# Pacman2-OSH-panels.net
KiCad netlist of a schematic drawn in EAGLE
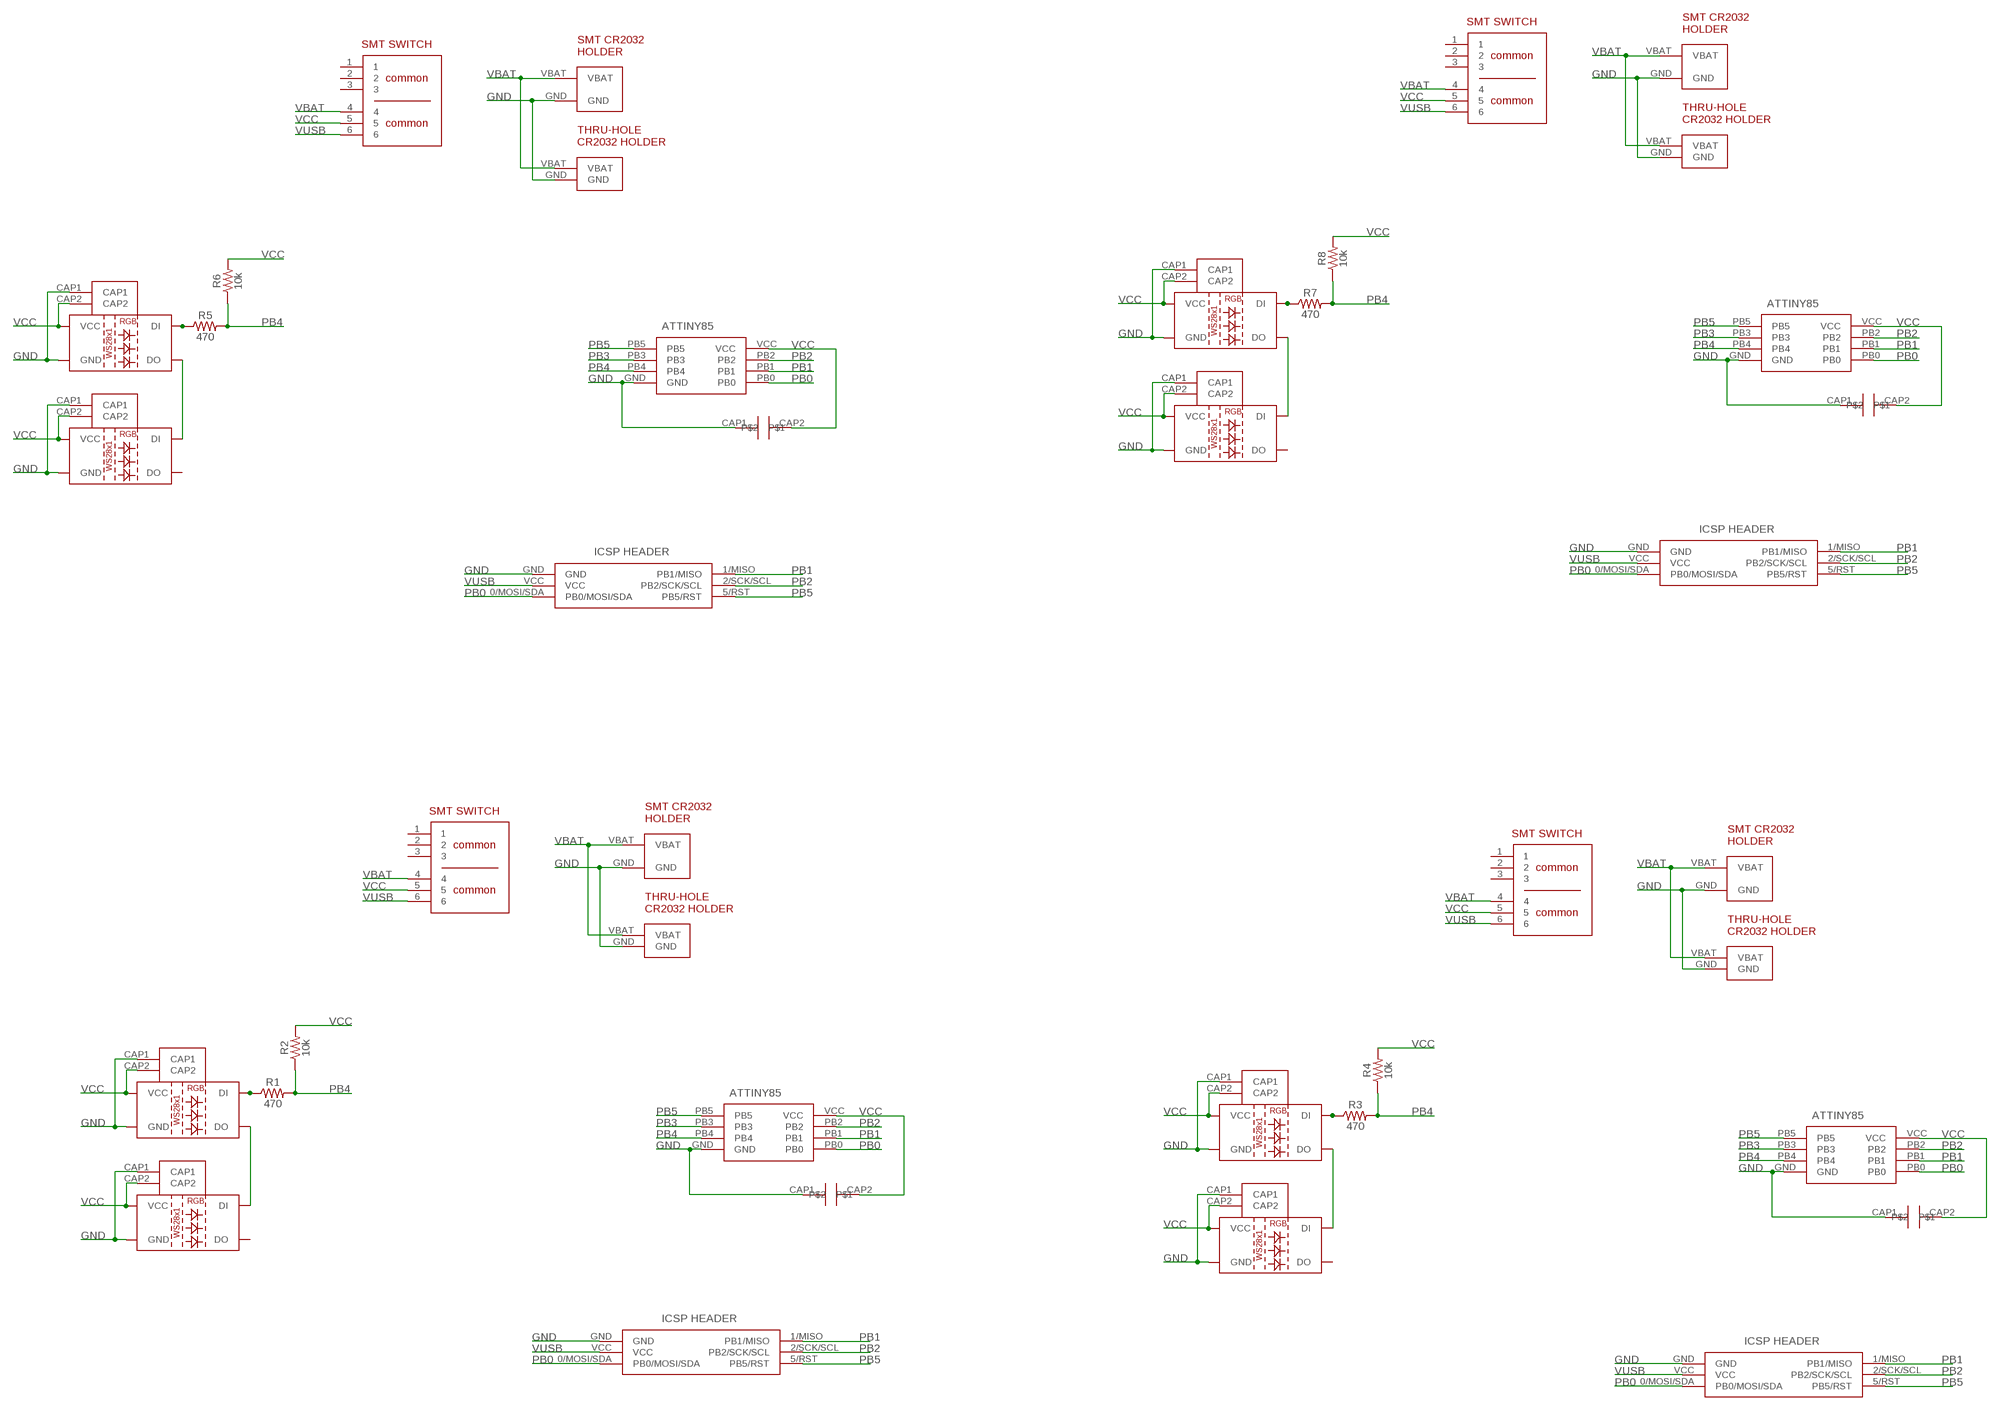
[diagram p0: schematic, sheet 1]

(export (version "E")
  (design (tool "Eeschema 10.0.6"))
  (components
    (comp (ref "D1")
      (value "WS2812B")
      (footprint "eagle-import:WS2812B")
      (libsource (lib "eagle-import") (part "WS2812B"))
    )
    (comp (ref "D2")
      (value "WS2812B")
      (footprint "eagle-import:WS2812B")
      (libsource (lib "eagle-import") (part "WS2812B"))
    )
    (comp (ref "D3")
      (value "WS2812B")
      (footprint "eagle-import:WS2812B")
      (libsource (lib "eagle-import") (part "WS2812B"))
    )
    (comp (ref "D4")
      (value "WS2812B")
      (footprint "eagle-import:WS2812B")
      (libsource (lib "eagle-import") (part "WS2812B"))
    )
    (comp (ref "D5")
      (value "WS2812B")
      (footprint "eagle-import:WS2812B")
      (libsource (lib "eagle-import") (part "WS2812B"))
    )
    (comp (ref "D6")
      (value "WS2812B")
      (footprint "eagle-import:WS2812B")
      (libsource (lib "eagle-import") (part "WS2812B"))
    )
    (comp (ref "D7")
      (value "WS2812B")
      (footprint "eagle-import:WS2812B")
      (libsource (lib "eagle-import") (part "WS2812B"))
    )
    (comp (ref "D8")
      (value "WS2812B")
      (footprint "eagle-import:WS2812B")
      (libsource (lib "eagle-import") (part "WS2812B"))
    )
    (comp (ref "DECOUPLER")
      (value ".1uf")
      (footprint "eagle-import:0603-CAP")
      (libsource (lib "eagle-import") (part "0603-CAP"))
    )
    (comp (ref "DECOUPLER1")
      (value ".1uf")
      (footprint "eagle-import:0603-CAP")
      (libsource (lib "eagle-import") (part "0603-CAP"))
    )
    (comp (ref "DECOUPLER2")
      (value ".1uf")
      (footprint "eagle-import:0603-CAP")
      (libsource (lib "eagle-import") (part "0603-CAP"))
    )
    (comp (ref "DECOUPLER3")
      (value ".1uf")
      (footprint "eagle-import:0603-CAP")
      (libsource (lib "eagle-import") (part "0603-CAP"))
    )
    (comp (ref "IC1")
      (value "ATTINY85-20SU")
      (footprint "eagle-import:SOT127P798X216-8N")
      (fields (field (name "RS_PART_NUMBER") "1331674"))
      (libsource (lib "eagle-import") (part "ATTINY85-20SU"))
    )
    (comp (ref "IC2")
      (value "ATTINY85-20SU")
      (footprint "eagle-import:SOT127P798X216-8N")
      (fields (field (name "RS_PART_NUMBER") "1331674"))
      (libsource (lib "eagle-import") (part "ATTINY85-20SU"))
    )
    (comp (ref "IC3")
      (value "ATTINY85-20SU")
      (footprint "eagle-import:SOT127P798X216-8N")
      (fields (field (name "RS_PART_NUMBER") "1331674"))
      (libsource (lib "eagle-import") (part "ATTINY85-20SU"))
    )
    (comp (ref "IC4")
      (value "ATTINY85-20SU")
      (footprint "eagle-import:SOT127P798X216-8N")
      (fields (field (name "RS_PART_NUMBER") "1331674"))
      (libsource (lib "eagle-import") (part "ATTINY85-20SU"))
    )
    (comp (ref "J1")
      (value "ICSP-LO-SILK")
      (footprint "eagle-import:ICSP-LO-SILK")
      (libsource (lib "eagle-import") (part "ICSP-LO-SILK"))
    )
    (comp (ref "J2")
      (value "ICSP-LO-SILK")
      (footprint "eagle-import:ICSP-LO-SILK")
      (libsource (lib "eagle-import") (part "ICSP-LO-SILK"))
    )
    (comp (ref "J3")
      (value "ICSP-LO-SILK")
      (footprint "eagle-import:ICSP-LO-SILK")
      (libsource (lib "eagle-import") (part "ICSP-LO-SILK"))
    )
    (comp (ref "J4")
      (value "ICSP-LO-SILK")
      (footprint "eagle-import:ICSP-LO-SILK")
      (libsource (lib "eagle-import") (part "ICSP-LO-SILK"))
    )
    (comp (ref "R1")
      (value "470")
      (footprint "eagle-import:0603")
      (libsource (lib "eagle-import") (part "470OHM-0603-1/10W-1%"))
    )
    (comp (ref "R2")
      (value "10k")
      (footprint "eagle-import:0603")
      (libsource (lib "eagle-import") (part "10KOHM-0603-1/10W-1%"))
    )
    (comp (ref "R3")
      (value "470")
      (footprint "eagle-import:0603")
      (libsource (lib "eagle-import") (part "470OHM-0603-1/10W-1%"))
    )
    (comp (ref "R4")
      (value "10k")
      (footprint "eagle-import:0603")
      (libsource (lib "eagle-import") (part "10KOHM-0603-1/10W-1%"))
    )
    (comp (ref "R5")
      (value "470")
      (footprint "eagle-import:0603")
      (libsource (lib "eagle-import") (part "470OHM-0603-1/10W-1%"))
    )
    (comp (ref "R6")
      (value "10k")
      (footprint "eagle-import:0603")
      (libsource (lib "eagle-import") (part "10KOHM-0603-1/10W-1%"))
    )
    (comp (ref "R7")
      (value "470")
      (footprint "eagle-import:0603")
      (libsource (lib "eagle-import") (part "470OHM-0603-1/10W-1%"))
    )
    (comp (ref "R8")
      (value "10k")
      (footprint "eagle-import:0603")
      (libsource (lib "eagle-import") (part "10KOHM-0603-1/10W-1%"))
    )
    (comp (ref "U$1")
      (value "SMT-SWITCH")
      (footprint "eagle-import:SMT-SWITCH")
      (libsource (lib "eagle-import") (part "SMT-SWITCH"))
    )
    (comp (ref "U$2")
      (value "SMT-BATTERY-HOLDER")
      (footprint "eagle-import:SMT-CR-HOLDER")
      (libsource (lib "eagle-import") (part "SMT-BATTERY-HOLDER"))
    )
    (comp (ref "U$3")
      (value "THRU-CR-HOLDER")
      (footprint "eagle-import:THRU-CR-HOLDER")
      (libsource (lib "eagle-import") (part "THRU-CR-HOLDER"))
    )
    (comp (ref "U$4")
      (value "SMT-BATTERY-HOLDER")
      (footprint "eagle-import:SMT-CR-HOLDER")
      (libsource (lib "eagle-import") (part "SMT-BATTERY-HOLDER"))
    )
    (comp (ref "U$5")
      (value "THRU-CR-HOLDER")
      (footprint "eagle-import:THRU-CR-HOLDER")
      (libsource (lib "eagle-import") (part "THRU-CR-HOLDER"))
    )
    (comp (ref "U$6")
      (value "SMT-SWITCH")
      (footprint "eagle-import:SMT-SWITCH")
      (libsource (lib "eagle-import") (part "SMT-SWITCH"))
    )
    (comp (ref "U$7")
      (value "SMT-BATTERY-HOLDER")
      (footprint "eagle-import:SMT-CR-HOLDER")
      (libsource (lib "eagle-import") (part "SMT-BATTERY-HOLDER"))
    )
    (comp (ref "U$8")
      (value "THRU-CR-HOLDER")
      (footprint "eagle-import:THRU-CR-HOLDER")
      (libsource (lib "eagle-import") (part "THRU-CR-HOLDER"))
    )
    (comp (ref "U$9")
      (value "SMT-SWITCH")
      (footprint "eagle-import:SMT-SWITCH")
      (libsource (lib "eagle-import") (part "SMT-SWITCH"))
    )
    (comp (ref "U$10")
      (value "SMT-BATTERY-HOLDER")
      (footprint "eagle-import:SMT-CR-HOLDER")
      (libsource (lib "eagle-import") (part "SMT-BATTERY-HOLDER"))
    )
    (comp (ref "U$11")
      (value "THRU-CR-HOLDER")
      (footprint "eagle-import:THRU-CR-HOLDER")
      (libsource (lib "eagle-import") (part "THRU-CR-HOLDER"))
    )
    (comp (ref "U$145")
      (value "SMT-SWITCH")
      (footprint "eagle-import:SMT-SWITCH")
      (libsource (lib "eagle-import") (part "SMT-SWITCH"))
    )
  )
  (nets
    (net (code "1") (name "/GND") (class "Default")
      (node (ref "D1") (pin "CAP1") (pinfunction "CAP1_CAP1") (pintype "bidirectional"))
      (node (ref "D1") (pin "GND") (pinfunction "GND_GND") (pintype "bidirectional"))
      (node (ref "D2") (pin "CAP1") (pinfunction "CAP1_CAP1") (pintype "bidirectional"))
      (node (ref "D2") (pin "GND") (pinfunction "GND_GND") (pintype "bidirectional"))
      (node (ref "D3") (pin "CAP1") (pinfunction "CAP1_CAP1") (pintype "bidirectional"))
      (node (ref "D3") (pin "GND") (pinfunction "GND_GND") (pintype "bidirectional"))
      (node (ref "D4") (pin "CAP1") (pinfunction "CAP1_CAP1") (pintype "bidirectional"))
      (node (ref "D4") (pin "GND") (pinfunction "GND_GND") (pintype "bidirectional"))
      (node (ref "D5") (pin "CAP1") (pinfunction "CAP1_CAP1") (pintype "bidirectional"))
      (node (ref "D5") (pin "GND") (pinfunction "GND_GND") (pintype "bidirectional"))
      (node (ref "D6") (pin "CAP1") (pinfunction "CAP1_CAP1") (pintype "bidirectional"))
      (node (ref "D6") (pin "GND") (pinfunction "GND_GND") (pintype "bidirectional"))
      (node (ref "D7") (pin "CAP1") (pinfunction "CAP1_CAP1") (pintype "bidirectional"))
      (node (ref "D7") (pin "GND") (pinfunction "GND_GND") (pintype "bidirectional"))
      (node (ref "D8") (pin "CAP1") (pinfunction "CAP1_CAP1") (pintype "bidirectional"))
      (node (ref "D8") (pin "GND") (pinfunction "GND_GND") (pintype "bidirectional"))
      (node (ref "DECOUPLER") (pin "CAP1") (pinfunction "P$1_CAP1") (pintype "bidirectional"))
      (node (ref "DECOUPLER1") (pin "CAP1") (pinfunction "P$1_CAP1") (pintype "bidirectional"))
      (node (ref "DECOUPLER2") (pin "CAP1") (pinfunction "P$1_CAP1") (pintype "bidirectional"))
      (node (ref "DECOUPLER3") (pin "CAP1") (pinfunction "P$1_CAP1") (pintype "bidirectional"))
      (node (ref "IC1") (pin "GND") (pinfunction "GND_GND") (pintype "bidirectional"))
      (node (ref "IC2") (pin "GND") (pinfunction "GND_GND") (pintype "bidirectional"))
      (node (ref "IC3") (pin "GND") (pinfunction "GND_GND") (pintype "bidirectional"))
      (node (ref "IC4") (pin "GND") (pinfunction "GND_GND") (pintype "bidirectional"))
      (node (ref "J1") (pin "GND") (pinfunction "GND_GND") (pintype "bidirectional"))
      (node (ref "J2") (pin "GND") (pinfunction "GND_GND") (pintype "bidirectional"))
      (node (ref "J3") (pin "GND") (pinfunction "GND_GND") (pintype "bidirectional"))
      (node (ref "J4") (pin "GND") (pinfunction "GND_GND") (pintype "bidirectional"))
      (node (ref "U$10") (pin "GND") (pinfunction "GND_GND") (pintype "bidirectional"))
      (node (ref "U$11") (pin "GND") (pinfunction "GND_GND") (pintype "bidirectional"))
      (node (ref "U$2") (pin "GND") (pinfunction "GND_GND") (pintype "bidirectional"))
      (node (ref "U$3") (pin "GND") (pinfunction "GND_GND") (pintype "bidirectional"))
      (node (ref "U$4") (pin "GND") (pinfunction "GND_GND") (pintype "bidirectional"))
      (node (ref "U$5") (pin "GND") (pinfunction "GND_GND") (pintype "bidirectional"))
      (node (ref "U$7") (pin "GND") (pinfunction "GND_GND") (pintype "bidirectional"))
      (node (ref "U$8") (pin "GND") (pinfunction "GND_GND") (pintype "bidirectional"))
    )
    (net (code "2") (name "/PB0") (class "Default")
      (node (ref "IC1") (pin "PB0") (pinfunction "PB0_PB0") (pintype "bidirectional"))
      (node (ref "IC2") (pin "PB0") (pinfunction "PB0_PB0") (pintype "bidirectional"))
      (node (ref "IC3") (pin "PB0") (pinfunction "PB0_PB0") (pintype "bidirectional"))
      (node (ref "IC4") (pin "PB0") (pinfunction "PB0_PB0") (pintype "bidirectional"))
      (node (ref "J1") (pin "0/MOSI/SDA") (pinfunction "PB0/MOSI/SDA_0/MOSI/SDA") (pintype "bidirectional"))
      (node (ref "J2") (pin "0/MOSI/SDA") (pinfunction "PB0/MOSI/SDA_0/MOSI/SDA") (pintype "bidirectional"))
      (node (ref "J3") (pin "0/MOSI/SDA") (pinfunction "PB0/MOSI/SDA_0/MOSI/SDA") (pintype "bidirectional"))
      (node (ref "J4") (pin "0/MOSI/SDA") (pinfunction "PB0/MOSI/SDA_0/MOSI/SDA") (pintype "bidirectional"))
    )
    (net (code "3") (name "/PB1") (class "Default")
      (node (ref "IC1") (pin "PB1") (pinfunction "PB1_PB1") (pintype "bidirectional"))
      (node (ref "IC2") (pin "PB1") (pinfunction "PB1_PB1") (pintype "bidirectional"))
      (node (ref "IC3") (pin "PB1") (pinfunction "PB1_PB1") (pintype "bidirectional"))
      (node (ref "IC4") (pin "PB1") (pinfunction "PB1_PB1") (pintype "bidirectional"))
      (node (ref "J1") (pin "1/MISO") (pinfunction "PB1/MISO_1/MISO") (pintype "bidirectional"))
      (node (ref "J2") (pin "1/MISO") (pinfunction "PB1/MISO_1/MISO") (pintype "bidirectional"))
      (node (ref "J3") (pin "1/MISO") (pinfunction "PB1/MISO_1/MISO") (pintype "bidirectional"))
      (node (ref "J4") (pin "1/MISO") (pinfunction "PB1/MISO_1/MISO") (pintype "bidirectional"))
    )
    (net (code "4") (name "/PB2") (class "Default")
      (node (ref "IC1") (pin "PB2") (pinfunction "PB2_PB2") (pintype "bidirectional"))
      (node (ref "IC2") (pin "PB2") (pinfunction "PB2_PB2") (pintype "bidirectional"))
      (node (ref "IC3") (pin "PB2") (pinfunction "PB2_PB2") (pintype "bidirectional"))
      (node (ref "IC4") (pin "PB2") (pinfunction "PB2_PB2") (pintype "bidirectional"))
      (node (ref "J1") (pin "2/SCK/SCL") (pinfunction "PB2/SCK/SCL_2/SCK/SCL") (pintype "bidirectional"))
      (node (ref "J2") (pin "2/SCK/SCL") (pinfunction "PB2/SCK/SCL_2/SCK/SCL") (pintype "bidirectional"))
      (node (ref "J3") (pin "2/SCK/SCL") (pinfunction "PB2/SCK/SCL_2/SCK/SCL") (pintype "bidirectional"))
      (node (ref "J4") (pin "2/SCK/SCL") (pinfunction "PB2/SCK/SCL_2/SCK/SCL") (pintype "bidirectional"))
    )
    (net (code "5") (name "/PB3") (class "Default")
      (node (ref "IC1") (pin "PB3") (pinfunction "PB3_PB3") (pintype "bidirectional"))
      (node (ref "IC2") (pin "PB3") (pinfunction "PB3_PB3") (pintype "bidirectional"))
      (node (ref "IC3") (pin "PB3") (pinfunction "PB3_PB3") (pintype "bidirectional"))
      (node (ref "IC4") (pin "PB3") (pinfunction "PB3_PB3") (pintype "bidirectional"))
    )
    (net (code "6") (name "/PB4") (class "Default")
      (node (ref "IC1") (pin "PB4") (pinfunction "PB4_PB4") (pintype "bidirectional"))
      (node (ref "IC2") (pin "PB4") (pinfunction "PB4_PB4") (pintype "bidirectional"))
      (node (ref "IC3") (pin "PB4") (pinfunction "PB4_PB4") (pintype "bidirectional"))
      (node (ref "IC4") (pin "PB4") (pinfunction "PB4_PB4") (pintype "bidirectional"))
      (node (ref "R1") (pin "2") (pinfunction "2_2") (pintype "passive"))
      (node (ref "R2") (pin "1") (pinfunction "1_1") (pintype "passive"))
      (node (ref "R3") (pin "2") (pinfunction "2_2") (pintype "passive"))
      (node (ref "R4") (pin "1") (pinfunction "1_1") (pintype "passive"))
      (node (ref "R5") (pin "2") (pinfunction "2_2") (pintype "passive"))
      (node (ref "R6") (pin "1") (pinfunction "1_1") (pintype "passive"))
      (node (ref "R7") (pin "2") (pinfunction "2_2") (pintype "passive"))
      (node (ref "R8") (pin "1") (pinfunction "1_1") (pintype "passive"))
    )
    (net (code "7") (name "/PB5") (class "Default")
      (node (ref "IC1") (pin "PB5") (pinfunction "PB5_PB5") (pintype "bidirectional"))
      (node (ref "IC2") (pin "PB5") (pinfunction "PB5_PB5") (pintype "bidirectional"))
      (node (ref "IC3") (pin "PB5") (pinfunction "PB5_PB5") (pintype "bidirectional"))
      (node (ref "IC4") (pin "PB5") (pinfunction "PB5_PB5") (pintype "bidirectional"))
      (node (ref "J1") (pin "5/RST") (pinfunction "PB5/RST_5/RST") (pintype "bidirectional"))
      (node (ref "J2") (pin "5/RST") (pinfunction "PB5/RST_5/RST") (pintype "bidirectional"))
      (node (ref "J3") (pin "5/RST") (pinfunction "PB5/RST_5/RST") (pintype "bidirectional"))
      (node (ref "J4") (pin "5/RST") (pinfunction "PB5/RST_5/RST") (pintype "bidirectional"))
    )
    (net (code "8") (name "/VBAT") (class "Default")
      (node (ref "U$1") (pin "4") (pinfunction "4_4") (pintype "bidirectional"))
      (node (ref "U$10") (pin "VBAT") (pinfunction "VBAT_VBAT") (pintype "bidirectional"))
      (node (ref "U$11") (pin "VBAT") (pinfunction "VBAT_VBAT") (pintype "bidirectional"))
      (node (ref "U$145") (pin "4") (pinfunction "4_4") (pintype "bidirectional"))
      (node (ref "U$2") (pin "VBAT") (pinfunction "VBAT_VBAT") (pintype "bidirectional"))
      (node (ref "U$3") (pin "VBAT") (pinfunction "VBAT_VBAT") (pintype "bidirectional"))
      (node (ref "U$4") (pin "VBAT") (pinfunction "VBAT_VBAT") (pintype "bidirectional"))
      (node (ref "U$5") (pin "VBAT") (pinfunction "VBAT_VBAT") (pintype "bidirectional"))
      (node (ref "U$6") (pin "4") (pinfunction "4_4") (pintype "bidirectional"))
      (node (ref "U$7") (pin "VBAT") (pinfunction "VBAT_VBAT") (pintype "bidirectional"))
      (node (ref "U$8") (pin "VBAT") (pinfunction "VBAT_VBAT") (pintype "bidirectional"))
      (node (ref "U$9") (pin "4") (pinfunction "4_4") (pintype "bidirectional"))
    )
    (net (code "9") (name "/VCC") (class "Default")
      (node (ref "D1") (pin "CAP2") (pinfunction "CAP2_CAP2") (pintype "bidirectional"))
      (node (ref "D1") (pin "VCC") (pinfunction "VCC_VCC") (pintype "bidirectional"))
      (node (ref "D2") (pin "CAP2") (pinfunction "CAP2_CAP2") (pintype "bidirectional"))
      (node (ref "D2") (pin "VCC") (pinfunction "VCC_VCC") (pintype "bidirectional"))
      (node (ref "D3") (pin "CAP2") (pinfunction "CAP2_CAP2") (pintype "bidirectional"))
      (node (ref "D3") (pin "VCC") (pinfunction "VCC_VCC") (pintype "bidirectional"))
      (node (ref "D4") (pin "CAP2") (pinfunction "CAP2_CAP2") (pintype "bidirectional"))
      (node (ref "D4") (pin "VCC") (pinfunction "VCC_VCC") (pintype "bidirectional"))
      (node (ref "D5") (pin "CAP2") (pinfunction "CAP2_CAP2") (pintype "bidirectional"))
      (node (ref "D5") (pin "VCC") (pinfunction "VCC_VCC") (pintype "bidirectional"))
      (node (ref "D6") (pin "CAP2") (pinfunction "CAP2_CAP2") (pintype "bidirectional"))
      (node (ref "D6") (pin "VCC") (pinfunction "VCC_VCC") (pintype "bidirectional"))
      (node (ref "D7") (pin "CAP2") (pinfunction "CAP2_CAP2") (pintype "bidirectional"))
      (node (ref "D7") (pin "VCC") (pinfunction "VCC_VCC") (pintype "bidirectional"))
      (node (ref "D8") (pin "CAP2") (pinfunction "CAP2_CAP2") (pintype "bidirectional"))
      (node (ref "D8") (pin "VCC") (pinfunction "VCC_VCC") (pintype "bidirectional"))
      (node (ref "DECOUPLER") (pin "CAP2") (pinfunction "P$2_CAP2") (pintype "bidirectional"))
      (node (ref "DECOUPLER1") (pin "CAP2") (pinfunction "P$2_CAP2") (pintype "bidirectional"))
      (node (ref "DECOUPLER2") (pin "CAP2") (pinfunction "P$2_CAP2") (pintype "bidirectional"))
      (node (ref "DECOUPLER3") (pin "CAP2") (pinfunction "P$2_CAP2") (pintype "bidirectional"))
      (node (ref "IC1") (pin "VCC") (pinfunction "VCC_VCC") (pintype "bidirectional"))
      (node (ref "IC2") (pin "VCC") (pinfunction "VCC_VCC") (pintype "bidirectional"))
      (node (ref "IC3") (pin "VCC") (pinfunction "VCC_VCC") (pintype "bidirectional"))
      (node (ref "IC4") (pin "VCC") (pinfunction "VCC_VCC") (pintype "bidirectional"))
      (node (ref "R2") (pin "2") (pinfunction "2_2") (pintype "passive"))
      (node (ref "R4") (pin "2") (pinfunction "2_2") (pintype "passive"))
      (node (ref "R6") (pin "2") (pinfunction "2_2") (pintype "passive"))
      (node (ref "R8") (pin "2") (pinfunction "2_2") (pintype "passive"))
      (node (ref "U$1") (pin "5") (pinfunction "5_5") (pintype "bidirectional"))
      (node (ref "U$145") (pin "5") (pinfunction "5_5") (pintype "bidirectional"))
      (node (ref "U$6") (pin "5") (pinfunction "5_5") (pintype "bidirectional"))
      (node (ref "U$9") (pin "5") (pinfunction "5_5") (pintype "bidirectional"))
    )
    (net (code "10") (name "/VUSB") (class "Default")
      (node (ref "J1") (pin "VCC") (pinfunction "VCC_VCC") (pintype "bidirectional"))
      (node (ref "J2") (pin "VCC") (pinfunction "VCC_VCC") (pintype "bidirectional"))
      (node (ref "J3") (pin "VCC") (pinfunction "VCC_VCC") (pintype "bidirectional"))
      (node (ref "J4") (pin "VCC") (pinfunction "VCC_VCC") (pintype "bidirectional"))
      (node (ref "U$1") (pin "6") (pinfunction "6_6") (pintype "bidirectional"))
      (node (ref "U$145") (pin "6") (pinfunction "6_6") (pintype "bidirectional"))
      (node (ref "U$6") (pin "6") (pinfunction "6_6") (pintype "bidirectional"))
      (node (ref "U$9") (pin "6") (pinfunction "6_6") (pintype "bidirectional"))
    )
    (net (code "11") (name "Net-(D1-PadDI)") (class "Default")
      (node (ref "D1") (pin "DI") (pinfunction "DI_DI") (pintype "bidirectional"))
      (node (ref "R1") (pin "1") (pinfunction "1_1") (pintype "passive"))
    )
    (net (code "12") (name "Net-(D1-PadDO)") (class "Default")
      (node (ref "D1") (pin "DO") (pinfunction "DO_DO") (pintype "bidirectional"))
      (node (ref "D2") (pin "DI") (pinfunction "DI_DI") (pintype "bidirectional"))
    )
    (net (code "13") (name "Net-(D3-PadDI)") (class "Default")
      (node (ref "D3") (pin "DI") (pinfunction "DI_DI") (pintype "bidirectional"))
      (node (ref "R3") (pin "1") (pinfunction "1_1") (pintype "passive"))
    )
    (net (code "14") (name "Net-(D3-PadDO)") (class "Default")
      (node (ref "D3") (pin "DO") (pinfunction "DO_DO") (pintype "bidirectional"))
      (node (ref "D4") (pin "DI") (pinfunction "DI_DI") (pintype "bidirectional"))
    )
    (net (code "15") (name "Net-(D5-PadDI)") (class "Default")
      (node (ref "D5") (pin "DI") (pinfunction "DI_DI") (pintype "bidirectional"))
      (node (ref "R5") (pin "1") (pinfunction "1_1") (pintype "passive"))
    )
    (net (code "16") (name "Net-(D5-PadDO)") (class "Default")
      (node (ref "D5") (pin "DO") (pinfunction "DO_DO") (pintype "bidirectional"))
      (node (ref "D6") (pin "DI") (pinfunction "DI_DI") (pintype "bidirectional"))
    )
    (net (code "17") (name "Net-(D7-PadDI)") (class "Default")
      (node (ref "D7") (pin "DI") (pinfunction "DI_DI") (pintype "bidirectional"))
      (node (ref "R7") (pin "1") (pinfunction "1_1") (pintype "passive"))
    )
    (net (code "18") (name "Net-(D7-PadDO)") (class "Default")
      (node (ref "D7") (pin "DO") (pinfunction "DO_DO") (pintype "bidirectional"))
      (node (ref "D8") (pin "DI") (pinfunction "DI_DI") (pintype "bidirectional"))
    )
    (net (code "19") (name "unconnected-(D2-PadDO)") (class "Default")
      (node (ref "D2") (pin "DO") (pinfunction "DO_DO") (pintype "bidirectional"))
    )
    (net (code "20") (name "unconnected-(D4-PadDO)") (class "Default")
      (node (ref "D4") (pin "DO") (pinfunction "DO_DO") (pintype "bidirectional"))
    )
    (net (code "21") (name "unconnected-(D6-PadDO)") (class "Default")
      (node (ref "D6") (pin "DO") (pinfunction "DO_DO") (pintype "bidirectional"))
    )
    (net (code "22") (name "unconnected-(D8-PadDO)") (class "Default")
      (node (ref "D8") (pin "DO") (pinfunction "DO_DO") (pintype "bidirectional"))
    )
    (net (code "23") (name "unconnected-(U$1-Pad1)") (class "Default")
      (node (ref "U$1") (pin "1") (pinfunction "1_1") (pintype "bidirectional"))
    )
    (net (code "24") (name "unconnected-(U$1-Pad2)") (class "Default")
      (node (ref "U$1") (pin "2") (pinfunction "2_2") (pintype "bidirectional"))
    )
    (net (code "25") (name "unconnected-(U$1-Pad3)") (class "Default")
      (node (ref "U$1") (pin "3") (pinfunction "3_3") (pintype "bidirectional"))
    )
    (net (code "26") (name "unconnected-(U$6-Pad1)") (class "Default")
      (node (ref "U$6") (pin "1") (pinfunction "1_1") (pintype "bidirectional"))
    )
    (net (code "27") (name "unconnected-(U$6-Pad2)") (class "Default")
      (node (ref "U$6") (pin "2") (pinfunction "2_2") (pintype "bidirectional"))
    )
    (net (code "28") (name "unconnected-(U$6-Pad3)") (class "Default")
      (node (ref "U$6") (pin "3") (pinfunction "3_3") (pintype "bidirectional"))
    )
    (net (code "29") (name "unconnected-(U$9-Pad1)") (class "Default")
      (node (ref "U$9") (pin "1") (pinfunction "1_1") (pintype "bidirectional"))
    )
    (net (code "30") (name "unconnected-(U$9-Pad2)") (class "Default")
      (node (ref "U$9") (pin "2") (pinfunction "2_2") (pintype "bidirectional"))
    )
    (net (code "31") (name "unconnected-(U$9-Pad3)") (class "Default")
      (node (ref "U$9") (pin "3") (pinfunction "3_3") (pintype "bidirectional"))
    )
    (net (code "32") (name "unconnected-(U$145-Pad1)") (class "Default")
      (node (ref "U$145") (pin "1") (pinfunction "1_1") (pintype "bidirectional"))
    )
    (net (code "33") (name "unconnected-(U$145-Pad2)") (class "Default")
      (node (ref "U$145") (pin "2") (pinfunction "2_2") (pintype "bidirectional"))
    )
    (net (code "34") (name "unconnected-(U$145-Pad3)") (class "Default")
      (node (ref "U$145") (pin "3") (pinfunction "3_3") (pintype "bidirectional"))
    )
  )
)
